# TowCam_Rev_A.net
KiCad netlist of a schematic drawn in EAGLE
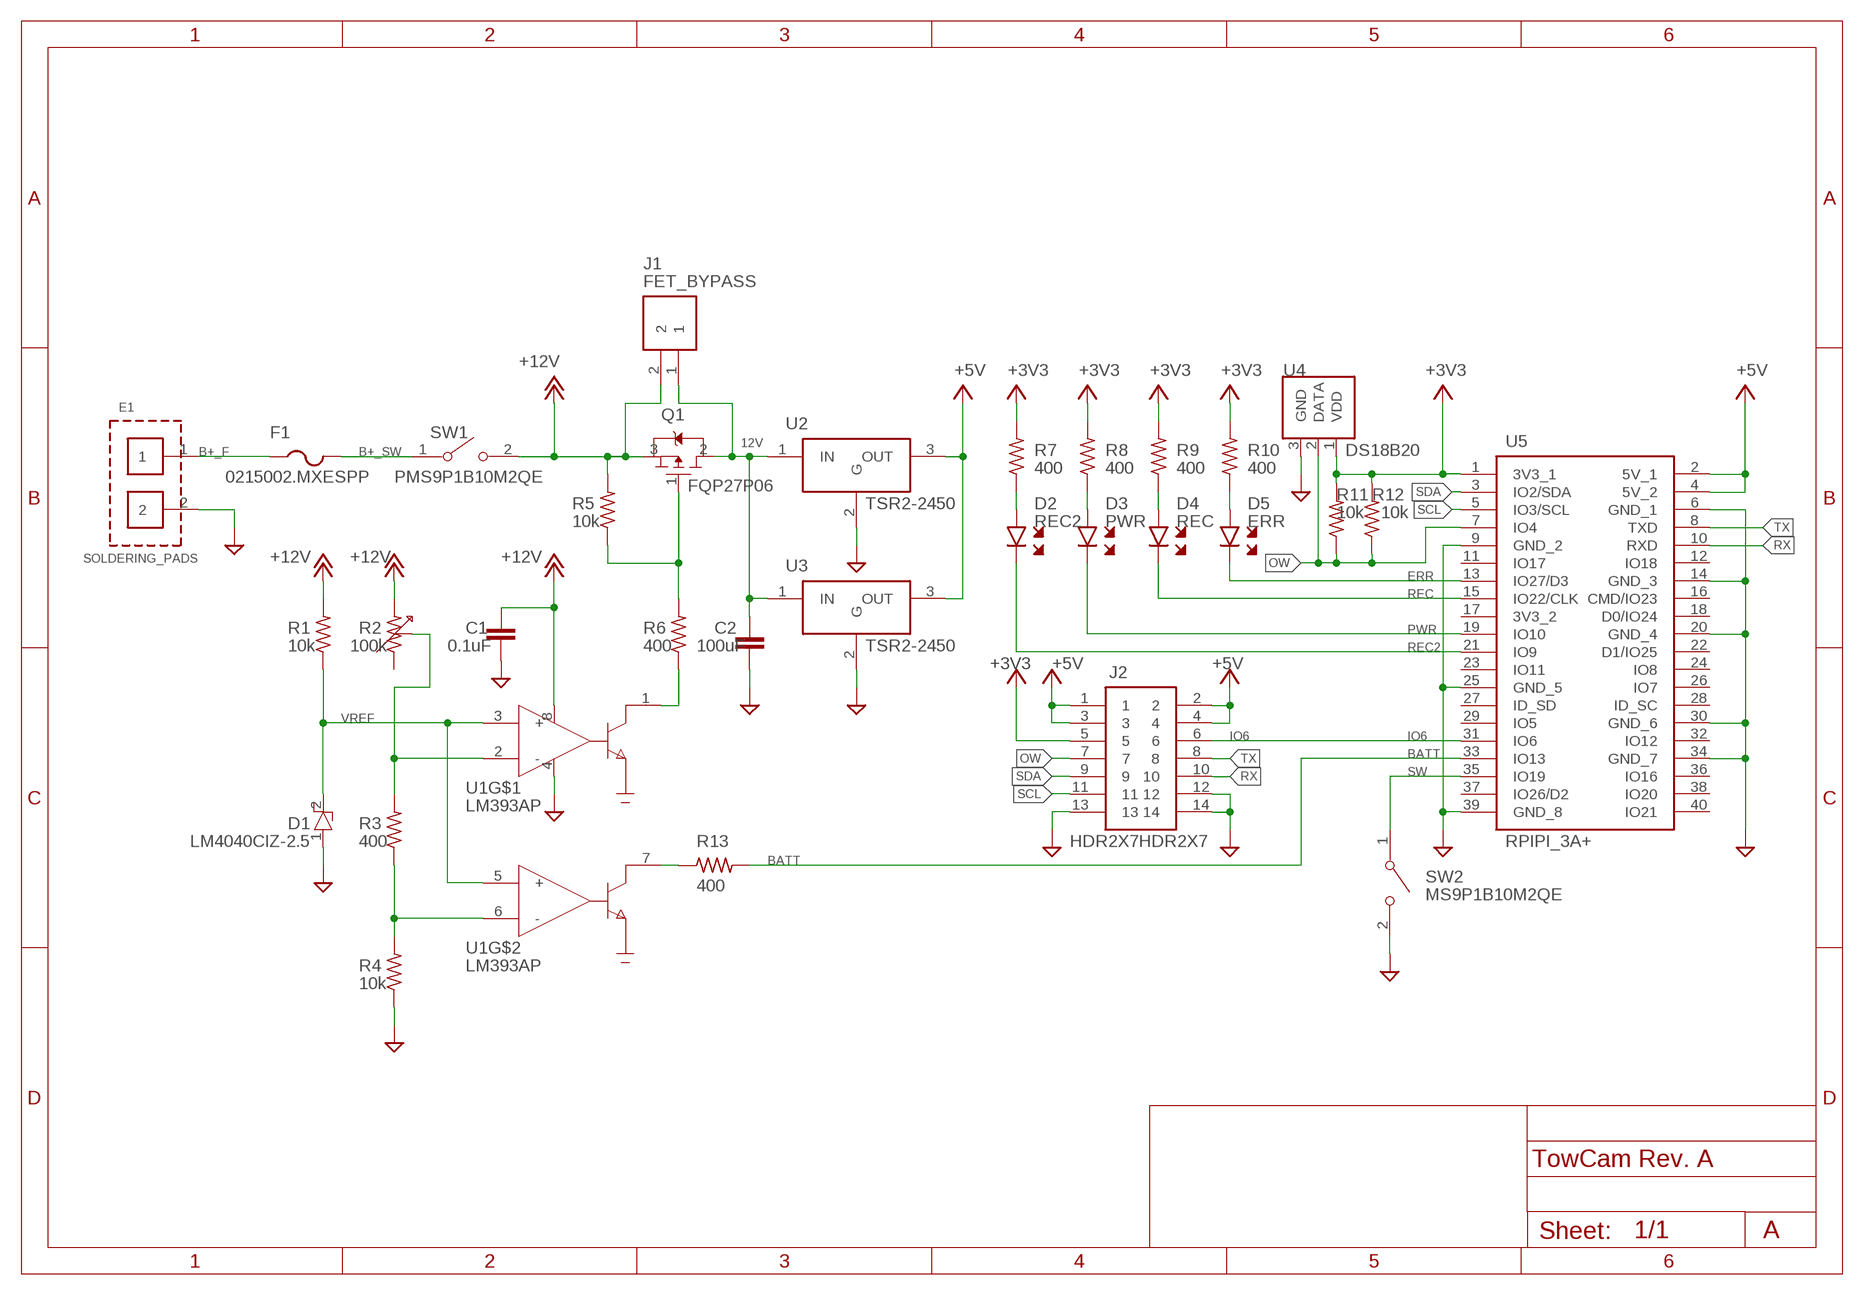
[diagram p0: schematic, sheet 1]

(export (version "E")
  (design (tool "Eeschema 10.0.6"))
  (components
    (comp (ref "C1")
      (value "0.1uF")
      (footprint "eagle-import:CAPPRD254W65D300H300B")
      (libsource (lib "eagle-import") (part "CAPACITORRAD-3MM"))
    )
    (comp (ref "C2")
      (value "100uF")
      (footprint "eagle-import:CAP-TH-5MM")
      (libsource (lib "eagle-import") (part "CAP_THCAP-TH-5MM"))
    )
    (comp (ref "D1")
      (value "LM4040CIZ-2.5")
      (footprint "eagle-import:TO-92")
      (libsource (lib "eagle-import") (part "ZENERLM4040CIZ-2.5"))
    )
    (comp (ref "D2")
      (value "REC2")
      (footprint "eagle-import:LEDRD254W60D565H860B")
      (libsource (lib "eagle-import") (part "LED_THLED-2.54"))
    )
    (comp (ref "D3")
      (value "PWR")
      (footprint "eagle-import:R0805")
      (libsource (lib "eagle-import") (part "LED0805"))
    )
    (comp (ref "D4")
      (value "REC")
      (footprint "eagle-import:R0805")
      (libsource (lib "eagle-import") (part "LED0805"))
    )
    (comp (ref "D5")
      (value "ERR")
      (footprint "eagle-import:R0805")
      (libsource (lib "eagle-import") (part "LED0805"))
    )
    (comp (ref "E1")
      (value "SOLDERING_PADS")
      (footprint "eagle-import:SOLDERING_PADS")
      (libsource (lib "eagle-import") (part "SOLDERING_PADS"))
    )
    (comp (ref "F1")
      (value "0215002.MXESPP")
      (footprint "eagle-import:0215002.MXESPP")
      (libsource (lib "eagle-import") (part "FUSE0215002.MXESPP"))
    )
    (comp (ref "J1")
      (value "FET_BYPASS")
      (footprint "eagle-import:HDR1X2")
      (libsource (lib "eagle-import") (part "HDR1X22P2.54MM"))
    )
    (comp (ref "J2")
      (value "HDR2X7HDR2X7")
      (footprint "eagle-import:HDR2X7")
      (libsource (lib "eagle-import") (part "HDR2X7HDR2X7"))
    )
    (comp (ref "Q1")
      (value "FQP27P06")
      (footprint "eagle-import:TO-220-BEND")
      (libsource (lib "eagle-import") (part "FQP27P06"))
    )
    (comp (ref "R1")
      (value "10k")
      (footprint "eagle-import:R0805")
      (libsource (lib "eagle-import") (part "RESISTOR0805"))
    )
    (comp (ref "R2")
      (value "100k")
      (footprint "eagle-import:PV36W104C01B00")
      (libsource (lib "eagle-import") (part "PV36W104C01B00"))
    )
    (comp (ref "R3")
      (value "400")
      (footprint "eagle-import:R0805")
      (libsource (lib "eagle-import") (part "RESISTOR0805"))
    )
    (comp (ref "R4")
      (value "10k")
      (footprint "eagle-import:R0805")
      (libsource (lib "eagle-import") (part "RESISTOR0805"))
    )
    (comp (ref "R5")
      (value "10k")
      (footprint "eagle-import:R0805")
      (libsource (lib "eagle-import") (part "RESISTOR0805"))
    )
    (comp (ref "R6")
      (value "400")
      (footprint "eagle-import:R0805")
      (libsource (lib "eagle-import") (part "RESISTOR0805"))
    )
    (comp (ref "R7")
      (value "400")
      (footprint "eagle-import:R0805")
      (libsource (lib "eagle-import") (part "RESISTOR0805"))
    )
    (comp (ref "R8")
      (value "400")
      (footprint "eagle-import:R0805")
      (libsource (lib "eagle-import") (part "RESISTOR0805"))
    )
    (comp (ref "R9")
      (value "400")
      (footprint "eagle-import:R0805")
      (libsource (lib "eagle-import") (part "RESISTOR0805"))
    )
    (comp (ref "R10")
      (value "400")
      (footprint "eagle-import:R0805")
      (libsource (lib "eagle-import") (part "RESISTOR0805"))
    )
    (comp (ref "R11")
      (value "10k")
      (footprint "eagle-import:R0805")
      (libsource (lib "eagle-import") (part "RESISTOR0805"))
    )
    (comp (ref "R12")
      (value "10k")
      (footprint "eagle-import:R0805")
      (libsource (lib "eagle-import") (part "RESISTOR0805"))
    )
    (comp (ref "R13")
      (value "400")
      (footprint "eagle-import:R0805")
      (libsource (lib "eagle-import") (part "RESISTOR0805"))
    )
    (comp (ref "SW1")
      (value "PMS9P1B10M2QE")
      (footprint "eagle-import:PMS9P1B10M2QE")
      (libsource (lib "eagle-import") (part "SPSTPMS9P1B10M2QE"))
    )
    (comp (ref "SW2")
      (value "MS9P1B10M2QE")
      (footprint "eagle-import:PMS9P1B10M2QE")
      (libsource (lib "eagle-import") (part "SPSTPMS9P1B10M2QE"))
    )
    (comp (ref "U1")
      (value "LM393AP")
      (footprint "eagle-import:DIP8")
      (libsource (lib "eagle-import") (part "LM393APDIP8"))
    )
    (comp (ref "U2")
      (value "TSR2-2450")
      (footprint "eagle-import:TSR2-2450")
      (libsource (lib "eagle-import") (part "TSR2-2450"))
    )
    (comp (ref "U3")
      (value "TSR2-2450")
      (footprint "eagle-import:TSR2-2450")
      (libsource (lib "eagle-import") (part "TSR2-2450"))
    )
    (comp (ref "U4")
      (value "DS18B20")
      (footprint "eagle-import:TO-92")
      (libsource (lib "eagle-import") (part "DS18B20"))
    )
    (comp (ref "U5")
      (value "RPIPI_3A+")
      (footprint "eagle-import:PI_3A+")
      (libsource (lib "eagle-import") (part "RPIPI_3A+"))
    )
  )
  (nets
    (net (code "1") (name "+3V3") (class "Default")
      (node (ref "J2") (pin "5") (pinfunction "5_5") (pintype "bidirectional"))
      (node (ref "R10") (pin "2") (pinfunction "2_2") (pintype "passive"))
      (node (ref "R11") (pin "2") (pinfunction "2_2") (pintype "passive"))
      (node (ref "R12") (pin "2") (pinfunction "2_2") (pintype "passive"))
      (node (ref "R7") (pin "2") (pinfunction "2_2") (pintype "passive"))
      (node (ref "R8") (pin "2") (pinfunction "2_2") (pintype "passive"))
      (node (ref "R9") (pin "2") (pinfunction "2_2") (pintype "passive"))
      (node (ref "U4") (pin "1") (pinfunction "VDD_1") (pintype "bidirectional"))
      (node (ref "U5") (pin "1") (pinfunction "3V3_1_1") (pintype "bidirectional"))
    )
    (net (code "2") (name "+5V") (class "Default")
      (node (ref "J2") (pin "1") (pinfunction "1_1") (pintype "bidirectional"))
      (node (ref "J2") (pin "2") (pinfunction "2_2") (pintype "bidirectional"))
      (node (ref "J2") (pin "3") (pinfunction "3_3") (pintype "bidirectional"))
      (node (ref "J2") (pin "4") (pinfunction "4_4") (pintype "bidirectional"))
      (node (ref "U2") (pin "3") (pinfunction "OUT_3") (pintype "bidirectional"))
      (node (ref "U3") (pin "3") (pinfunction "OUT_3") (pintype "bidirectional"))
      (node (ref "U5") (pin "2") (pinfunction "5V_1_2") (pintype "bidirectional"))
      (node (ref "U5") (pin "4") (pinfunction "5V_2_4") (pintype "bidirectional"))
    )
    (net (code "3") (name "+12V") (class "Default")
      (node (ref "C1") (pin "1") (pinfunction "1_1") (pintype "passive"))
      (node (ref "J1") (pin "2") (pinfunction "2_2") (pintype "bidirectional"))
      (node (ref "Q1") (pin "3") (pinfunction "S_3") (pintype "bidirectional"))
      (node (ref "R1") (pin "2") (pinfunction "2_2") (pintype "passive"))
      (node (ref "R2") (pin "3") (pinfunction "3_3") (pintype "passive"))
      (node (ref "R5") (pin "2") (pinfunction "2_2") (pintype "passive"))
      (node (ref "SW1") (pin "2") (pinfunction "P$2_2") (pintype "bidirectional"))
      (node (ref "U1") (pin "8") (pinfunction "VCC_8") (pintype "bidirectional"))
    )
    (net (code "4") (name "/12V") (class "Default")
      (node (ref "C2") (pin "1") (pinfunction "1_1") (pintype "passive"))
      (node (ref "J1") (pin "1") (pinfunction "1_1") (pintype "bidirectional"))
      (node (ref "Q1") (pin "2") (pinfunction "D_2") (pintype "bidirectional"))
      (node (ref "U2") (pin "1") (pinfunction "IN_1") (pintype "bidirectional"))
      (node (ref "U3") (pin "1") (pinfunction "IN_1") (pintype "bidirectional"))
    )
    (net (code "5") (name "/B+_F") (class "Default")
      (node (ref "E1") (pin "1") (pinfunction "1_1") (pintype "bidirectional"))
      (node (ref "F1") (pin "1") (pinfunction "1_1") (pintype "passive"))
    )
    (net (code "6") (name "/B+_SW") (class "Default")
      (node (ref "F1") (pin "2") (pinfunction "2_2") (pintype "passive"))
      (node (ref "SW1") (pin "1") (pinfunction "P$1_1") (pintype "bidirectional"))
    )
    (net (code "7") (name "/BATT") (class "Default")
      (node (ref "R13") (pin "2") (pinfunction "2_2") (pintype "passive"))
      (node (ref "U5") (pin "33") (pinfunction "IO13_33") (pintype "bidirectional"))
    )
    (net (code "8") (name "/ERR") (class "Default")
      (node (ref "D5") (pin "2") (pinfunction "P$2_2") (pintype "bidirectional"))
      (node (ref "U5") (pin "13") (pinfunction "IO27/D3_13") (pintype "bidirectional"))
    )
    (net (code "9") (name "/IO6") (class "Default")
      (node (ref "J2") (pin "6") (pinfunction "6_6") (pintype "bidirectional"))
      (node (ref "U5") (pin "31") (pinfunction "IO6_31") (pintype "bidirectional"))
    )
    (net (code "10") (name "/PWR") (class "Default")
      (node (ref "D3") (pin "2") (pinfunction "P$2_2") (pintype "bidirectional"))
      (node (ref "U5") (pin "19") (pinfunction "IO10_19") (pintype "bidirectional"))
    )
    (net (code "11") (name "/REC") (class "Default")
      (node (ref "D4") (pin "2") (pinfunction "P$2_2") (pintype "bidirectional"))
      (node (ref "U5") (pin "15") (pinfunction "IO22/CLK_15") (pintype "bidirectional"))
    )
    (net (code "12") (name "/REC2") (class "Default")
      (node (ref "D2") (pin "2") (pinfunction "P$2_2") (pintype "bidirectional"))
      (node (ref "U5") (pin "21") (pinfunction "IO9_21") (pintype "bidirectional"))
    )
    (net (code "13") (name "/SW") (class "Default")
      (node (ref "SW2") (pin "1") (pinfunction "P$1_1") (pintype "bidirectional"))
      (node (ref "U5") (pin "35") (pinfunction "IO19_35") (pintype "bidirectional"))
    )
    (net (code "14") (name "/VREF") (class "Default")
      (node (ref "D1") (pin "2") (pinfunction "C_2") (pintype "bidirectional"))
      (node (ref "R1") (pin "1") (pinfunction "1_1") (pintype "passive"))
      (node (ref "U1") (pin "3") (pinfunction "+_3") (pintype "bidirectional"))
      (node (ref "U1") (pin "5") (pinfunction "+_5") (pintype "bidirectional"))
    )
    (net (code "15") (name "GND") (class "Default")
      (node (ref "C1") (pin "2") (pinfunction "2_2") (pintype "passive"))
      (node (ref "C2") (pin "2") (pinfunction "2_2") (pintype "passive"))
      (node (ref "D1") (pin "1") (pinfunction "A_1") (pintype "bidirectional"))
      (node (ref "E1") (pin "2") (pinfunction "2_2") (pintype "bidirectional"))
      (node (ref "J2") (pin "12") (pinfunction "12_12") (pintype "bidirectional"))
      (node (ref "J2") (pin "13") (pinfunction "13_13") (pintype "bidirectional"))
      (node (ref "J2") (pin "14") (pinfunction "14_14") (pintype "bidirectional"))
      (node (ref "R4") (pin "1") (pinfunction "1_1") (pintype "passive"))
      (node (ref "SW2") (pin "2") (pinfunction "P$2_2") (pintype "bidirectional"))
      (node (ref "U1") (pin "4") (pinfunction "GND_4") (pintype "bidirectional"))
      (node (ref "U2") (pin "2") (pinfunction "G_2") (pintype "bidirectional"))
      (node (ref "U3") (pin "2") (pinfunction "G_2") (pintype "bidirectional"))
      (node (ref "U4") (pin "3") (pinfunction "GND_3") (pintype "bidirectional"))
      (node (ref "U5") (pin "14") (pinfunction "GND_3_14") (pintype "bidirectional"))
      (node (ref "U5") (pin "20") (pinfunction "GND_4_20") (pintype "bidirectional"))
      (node (ref "U5") (pin "25") (pinfunction "GND_5_25") (pintype "bidirectional"))
      (node (ref "U5") (pin "30") (pinfunction "GND_6_30") (pintype "bidirectional"))
      (node (ref "U5") (pin "34") (pinfunction "GND_7_34") (pintype "bidirectional"))
      (node (ref "U5") (pin "39") (pinfunction "GND_8_39") (pintype "bidirectional"))
      (node (ref "U5") (pin "6") (pinfunction "GND_1_6") (pintype "bidirectional"))
      (node (ref "U5") (pin "9") (pinfunction "GND_2_9") (pintype "bidirectional"))
    )
    (net (code "16") (name "Net-(D2-P$1)") (class "Default")
      (node (ref "D2") (pin "1") (pinfunction "P$1_1") (pintype "bidirectional"))
      (node (ref "R7") (pin "1") (pinfunction "1_1") (pintype "passive"))
    )
    (net (code "17") (name "Net-(D3-P$1)") (class "Default")
      (node (ref "D3") (pin "1") (pinfunction "P$1_1") (pintype "bidirectional"))
      (node (ref "R8") (pin "1") (pinfunction "1_1") (pintype "passive"))
    )
    (net (code "18") (name "Net-(D4-P$1)") (class "Default")
      (node (ref "D4") (pin "1") (pinfunction "P$1_1") (pintype "bidirectional"))
      (node (ref "R9") (pin "1") (pinfunction "1_1") (pintype "passive"))
    )
    (net (code "19") (name "Net-(D5-P$1)") (class "Default")
      (node (ref "D5") (pin "1") (pinfunction "P$1_1") (pintype "bidirectional"))
      (node (ref "R10") (pin "1") (pinfunction "1_1") (pintype "passive"))
    )
    (net (code "20") (name "Net-(Q1-G)") (class "Default")
      (node (ref "Q1") (pin "1") (pinfunction "G_1") (pintype "bidirectional"))
      (node (ref "R5") (pin "1") (pinfunction "1_1") (pintype "passive"))
      (node (ref "R6") (pin "2") (pinfunction "2_2") (pintype "passive"))
    )
    (net (code "21") (name "Net-(U1A--)") (class "Default")
      (node (ref "R2") (pin "2") (pinfunction "2_2") (pintype "bidirectional"))
      (node (ref "R3") (pin "2") (pinfunction "2_2") (pintype "passive"))
      (node (ref "U1") (pin "2") (pinfunction "-_2") (pintype "bidirectional"))
    )
    (net (code "22") (name "Net-(U1A-OUT)") (class "Default")
      (node (ref "R6") (pin "1") (pinfunction "1_1") (pintype "passive"))
      (node (ref "U1") (pin "1") (pinfunction "OUT_1") (pintype "bidirectional"))
    )
    (net (code "23") (name "Net-(U1B--)") (class "Default")
      (node (ref "R3") (pin "1") (pinfunction "1_1") (pintype "passive"))
      (node (ref "R4") (pin "2") (pinfunction "2_2") (pintype "passive"))
      (node (ref "U1") (pin "6") (pinfunction "-_6") (pintype "bidirectional"))
    )
    (net (code "24") (name "Net-(U1B-OUT)") (class "Default")
      (node (ref "R13") (pin "1") (pinfunction "1_1") (pintype "passive"))
      (node (ref "U1") (pin "7") (pinfunction "OUT_7") (pintype "bidirectional"))
    )
    (net (code "25") (name "OW") (class "Default")
      (node (ref "J2") (pin "7") (pinfunction "7_7") (pintype "bidirectional"))
      (node (ref "R11") (pin "1") (pinfunction "1_1") (pintype "passive"))
      (node (ref "R12") (pin "1") (pinfunction "1_1") (pintype "passive"))
      (node (ref "U4") (pin "2") (pinfunction "DATA_2") (pintype "bidirectional"))
      (node (ref "U5") (pin "7") (pinfunction "IO4_7") (pintype "bidirectional"))
    )
    (net (code "26") (name "RX") (class "Default")
      (node (ref "J2") (pin "10") (pinfunction "10_10") (pintype "bidirectional"))
      (node (ref "U5") (pin "10") (pinfunction "RXD_10") (pintype "bidirectional"))
    )
    (net (code "27") (name "SCL") (class "Default")
      (node (ref "J2") (pin "11") (pinfunction "11_11") (pintype "bidirectional"))
      (node (ref "U5") (pin "5") (pinfunction "IO3/SCL_5") (pintype "bidirectional"))
    )
    (net (code "28") (name "SDA") (class "Default")
      (node (ref "J2") (pin "9") (pinfunction "9_9") (pintype "bidirectional"))
      (node (ref "U5") (pin "3") (pinfunction "IO2/SDA_3") (pintype "bidirectional"))
    )
    (net (code "29") (name "TX") (class "Default")
      (node (ref "J2") (pin "8") (pinfunction "8_8") (pintype "bidirectional"))
      (node (ref "U5") (pin "8") (pinfunction "TXD_8") (pintype "bidirectional"))
    )
    (net (code "30") (name "unconnected-(R2-Pad1)") (class "Default")
      (node (ref "R2") (pin "1") (pinfunction "1_1") (pintype "passive"))
    )
    (net (code "31") (name "unconnected-(U5-3V3_2-Pad17)") (class "Default")
      (node (ref "U5") (pin "17") (pinfunction "3V3_2_17") (pintype "bidirectional"))
    )
    (net (code "32") (name "unconnected-(U5-CMD{slash}IO23-Pad16)") (class "Default")
      (node (ref "U5") (pin "16") (pinfunction "CMD/IO23_16") (pintype "bidirectional"))
    )
    (net (code "33") (name "unconnected-(U5-D0{slash}IO24-Pad18)") (class "Default")
      (node (ref "U5") (pin "18") (pinfunction "D0/IO24_18") (pintype "bidirectional"))
    )
    (net (code "34") (name "unconnected-(U5-D1{slash}IO25-Pad22)") (class "Default")
      (node (ref "U5") (pin "22") (pinfunction "D1/IO25_22") (pintype "bidirectional"))
    )
    (net (code "35") (name "unconnected-(U5-ID_SC-Pad28)") (class "Default")
      (node (ref "U5") (pin "28") (pinfunction "ID_SC_28") (pintype "bidirectional"))
    )
    (net (code "36") (name "unconnected-(U5-ID_SD-Pad27)") (class "Default")
      (node (ref "U5") (pin "27") (pinfunction "ID_SD_27") (pintype "bidirectional"))
    )
    (net (code "37") (name "unconnected-(U5-IO5-Pad29)") (class "Default")
      (node (ref "U5") (pin "29") (pinfunction "IO5_29") (pintype "bidirectional"))
    )
    (net (code "38") (name "unconnected-(U5-IO7-Pad26)") (class "Default")
      (node (ref "U5") (pin "26") (pinfunction "IO7_26") (pintype "bidirectional"))
    )
    (net (code "39") (name "unconnected-(U5-IO8-Pad24)") (class "Default")
      (node (ref "U5") (pin "24") (pinfunction "IO8_24") (pintype "bidirectional"))
    )
    (net (code "40") (name "unconnected-(U5-IO11-Pad23)") (class "Default")
      (node (ref "U5") (pin "23") (pinfunction "IO11_23") (pintype "bidirectional"))
    )
    (net (code "41") (name "unconnected-(U5-IO12-Pad32)") (class "Default")
      (node (ref "U5") (pin "32") (pinfunction "IO12_32") (pintype "bidirectional"))
    )
    (net (code "42") (name "unconnected-(U5-IO16-Pad36)") (class "Default")
      (node (ref "U5") (pin "36") (pinfunction "IO16_36") (pintype "bidirectional"))
    )
    (net (code "43") (name "unconnected-(U5-IO17-Pad11)") (class "Default")
      (node (ref "U5") (pin "11") (pinfunction "IO17_11") (pintype "bidirectional"))
    )
    (net (code "44") (name "unconnected-(U5-IO18-Pad12)") (class "Default")
      (node (ref "U5") (pin "12") (pinfunction "IO18_12") (pintype "bidirectional"))
    )
    (net (code "45") (name "unconnected-(U5-IO20-Pad38)") (class "Default")
      (node (ref "U5") (pin "38") (pinfunction "IO20_38") (pintype "bidirectional"))
    )
    (net (code "46") (name "unconnected-(U5-IO21-Pad40)") (class "Default")
      (node (ref "U5") (pin "40") (pinfunction "IO21_40") (pintype "bidirectional"))
    )
    (net (code "47") (name "unconnected-(U5-IO26{slash}D2-Pad37)") (class "Default")
      (node (ref "U5") (pin "37") (pinfunction "IO26/D2_37") (pintype "bidirectional"))
    )
  )
)
